# M4-Shim-1.net
KiCad netlist of a schematic drawn in EAGLE
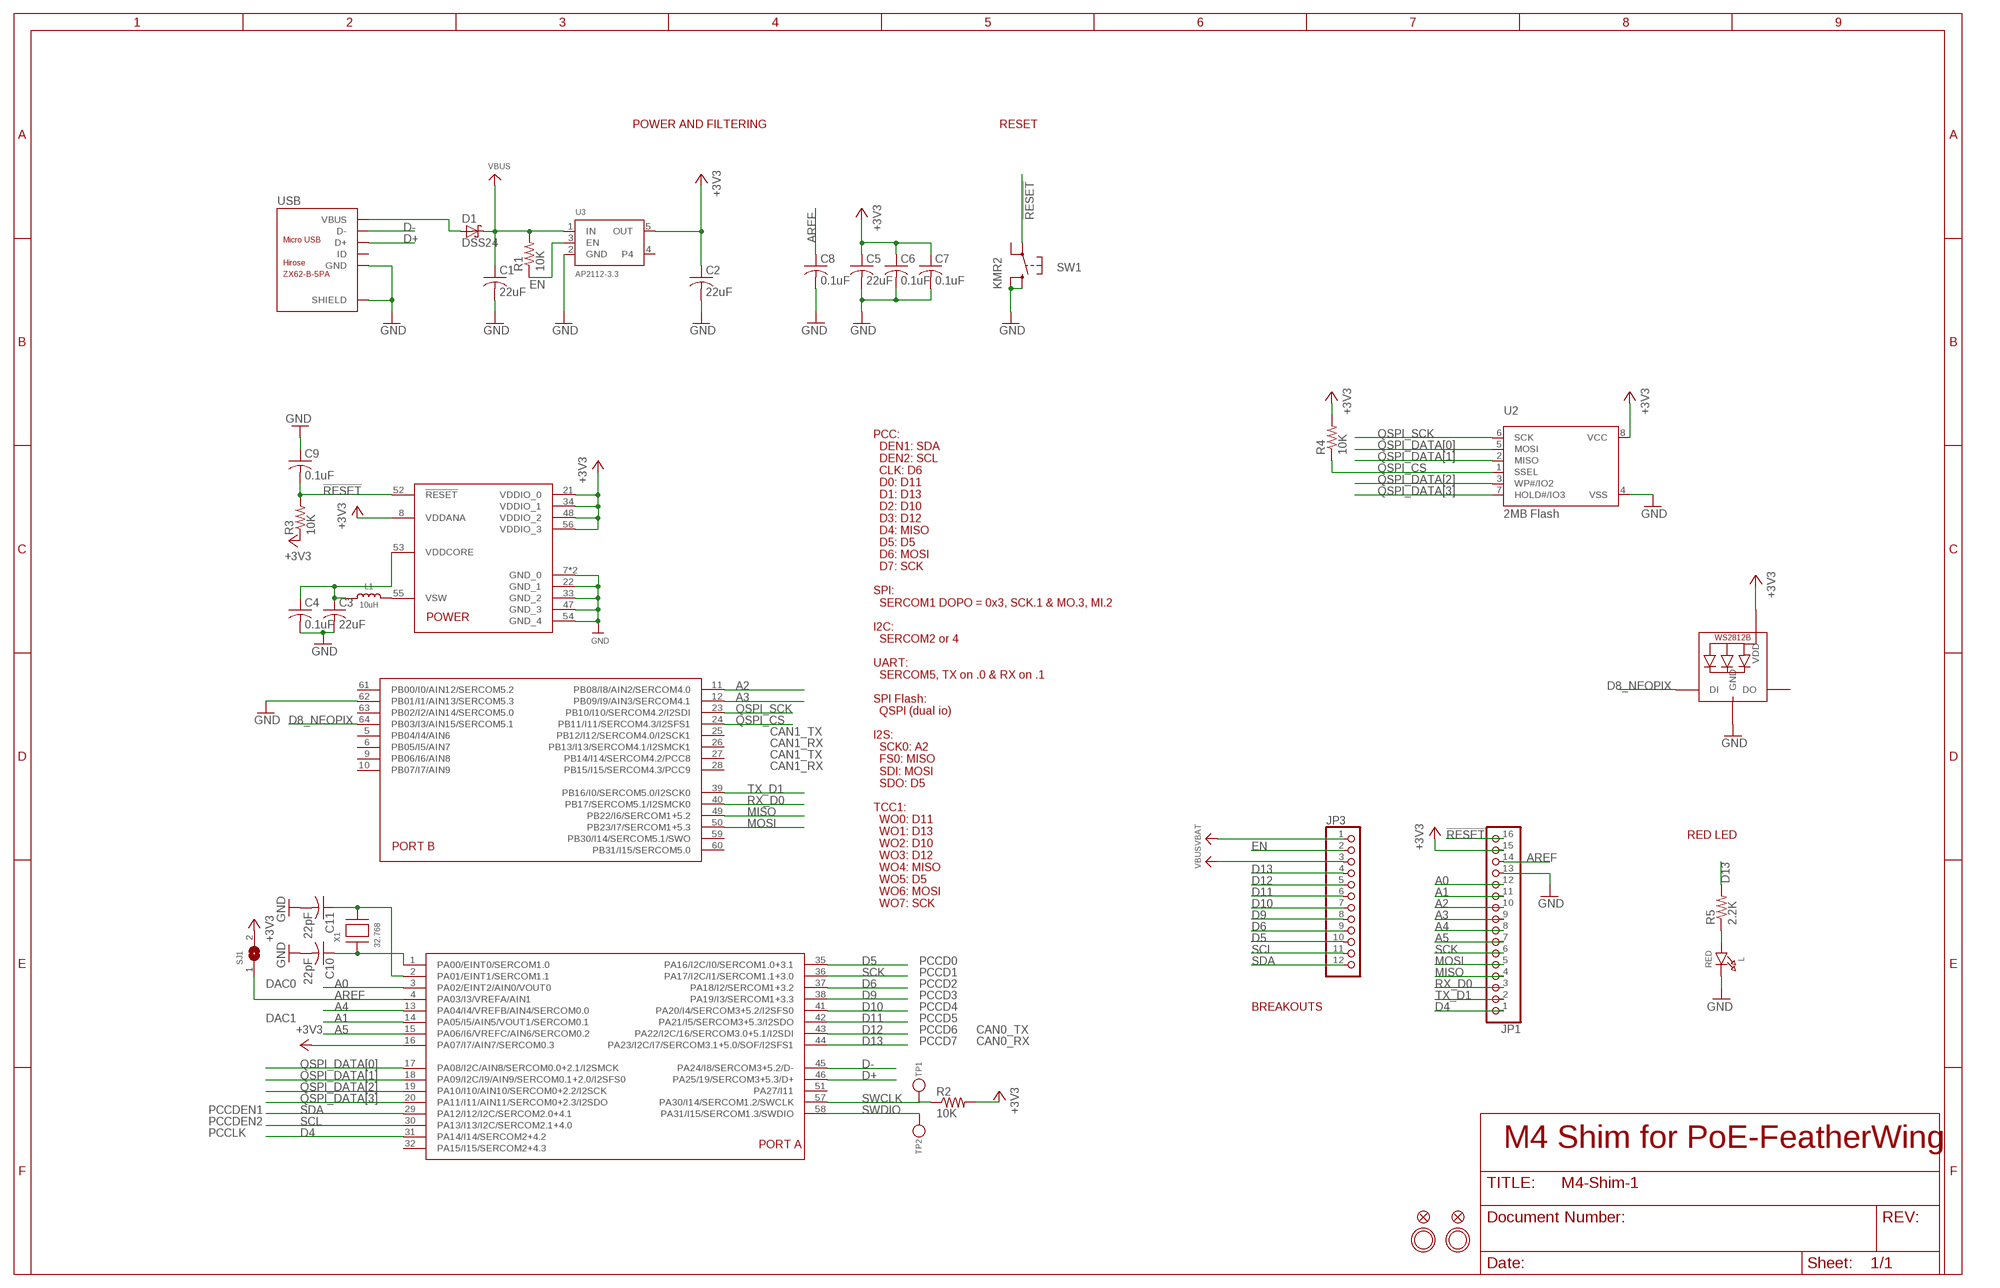
[diagram p0: schematic, sheet 1]

(export (version "E")
  (design (tool "Eeschema 10.0.6"))
  (components
    (comp (ref "C1")
      (value "22uF")
      (footprint "eagle-import:C0805K")
      (libsource (lib "eagle-import") (part "C-USC0805K"))
    )
    (comp (ref "C2")
      (value "22uF")
      (footprint "eagle-import:C0805K")
      (libsource (lib "eagle-import") (part "C-USC0805K"))
    )
    (comp (ref "C3")
      (value "22uF")
      (footprint "eagle-import:C0805K")
      (libsource (lib "eagle-import") (part "C-USC0805K"))
    )
    (comp (ref "C4")
      (value "0.1uF")
      (footprint "eagle-import:C0402K")
      (libsource (lib "eagle-import") (part "C-USC0402K"))
    )
    (comp (ref "C5")
      (value "22uF")
      (footprint "eagle-import:C0805K")
      (libsource (lib "eagle-import") (part "C-USC0805K"))
    )
    (comp (ref "C6")
      (value "0.1uF")
      (footprint "eagle-import:C0402K")
      (libsource (lib "eagle-import") (part "C-USC0402K"))
    )
    (comp (ref "C7")
      (value "0.1uF")
      (footprint "eagle-import:C0402K")
      (libsource (lib "eagle-import") (part "C-USC0402K"))
    )
    (comp (ref "C8")
      (value "0.1uF")
      (footprint "eagle-import:C0402K")
      (libsource (lib "eagle-import") (part "C-USC0402K"))
    )
    (comp (ref "C9")
      (value "0.1uF")
      (footprint "eagle-import:C0402K")
      (libsource (lib "eagle-import") (part "C-USC0402K"))
    )
    (comp (ref "C10")
      (value "22pF")
      (footprint "eagle-import:C0402K")
      (libsource (lib "eagle-import") (part "C-USC0402K"))
    )
    (comp (ref "C11")
      (value "22pF")
      (footprint "eagle-import:C0402K")
      (libsource (lib "eagle-import") (part "C-USC0402K"))
    )
    (comp (ref "D1")
      (value "DSS24")
      (footprint "eagle-import:SOD123FL")
      (libsource (lib "eagle-import") (part "DSS24"))
    )
    (comp (ref "JP1")
      (value "HEADER-1X16ROUND")
      (footprint "eagle-import:1X16_ROUND")
      (libsource (lib "eagle-import") (part "HEADER-1X16ROUND"))
    )
    (comp (ref "JP3")
      (value "HEADER-1X12")
      (footprint "eagle-import:1X12_ROUND")
      (libsource (lib "eagle-import") (part "HEADER-1X12"))
    )
    (comp (ref "L")
      (value "RED")
      (footprint "eagle-import:CHIPLED_0805_NOOUTLINE")
      (libsource (lib "eagle-import") (part "LED0805_NOOUTLINE"))
    )
    (comp (ref "L1")
      (value "10uH")
      (footprint "eagle-import:INDUCTOR_1007")
      (libsource (lib "eagle-import") (part "INDUCTOR"))
    )
    (comp (ref "LED1")
      (value "WS2812B3535")
      (footprint "eagle-import:LED3535")
      (libsource (lib "eagle-import") (part "WS2812B3535"))
    )
    (comp (ref "R1")
      (value "10K")
      (footprint "eagle-import:R0402")
      (libsource (lib "eagle-import") (part "R-US_R0402"))
    )
    (comp (ref "R2")
      (value "10K")
      (footprint "eagle-import:R0402")
      (libsource (lib "eagle-import") (part "R-US_R0402"))
    )
    (comp (ref "R3")
      (value "10K")
      (footprint "eagle-import:R0402")
      (libsource (lib "eagle-import") (part "R-US_R0402"))
    )
    (comp (ref "R4")
      (value "10K")
      (footprint "eagle-import:R0402")
      (libsource (lib "eagle-import") (part "R-US_R0402"))
    )
    (comp (ref "R5")
      (value "2.2K")
      (footprint "eagle-import:R0402")
      (libsource (lib "eagle-import") (part "R-US_R0402"))
    )
    (comp (ref "SJ1")
      (value "SOLDERJUMPERCLOSED")
      (footprint "eagle-import:SOLDERJUMPER_CLOSEDWIRE")
      (libsource (lib "eagle-import") (part "SOLDERJUMPERCLOSED"))
    )
    (comp (ref "SW1")
      (value "KMR2")
      (footprint "eagle-import:BTN_KMR2_4.6X2.8")
      (libsource (lib "eagle-import") (part "SWITCH_TACT_SMT4.6X2.8"))
    )
    (comp (ref "TP1")
      (value "TESTPOINTROUND1.5MM")
      (footprint "eagle-import:TESTPOINT_ROUND_1.5MM")
      (libsource (lib "eagle-import") (part "TESTPOINTROUND1.5MM"))
    )
    (comp (ref "TP2")
      (value "TESTPOINTROUND1.5MM")
      (footprint "eagle-import:TESTPOINT_ROUND_1.5MM")
      (libsource (lib "eagle-import") (part "TESTPOINTROUND1.5MM"))
    )
    (comp (ref "U$31")
      (value "MOUNTINGHOLE2.5")
      (footprint "eagle-import:MOUNTINGHOLE_2.5_PLATED")
      (libsource (lib "eagle-import") (part "MOUNTINGHOLE2.5"))
    )
    (comp (ref "U$32")
      (value "MOUNTINGHOLE2.5")
      (footprint "eagle-import:MOUNTINGHOLE_2.5_PLATED")
      (libsource (lib "eagle-import") (part "MOUNTINGHOLE2.5"))
    )
    (comp (ref "U$34")
      (value "FIDUCIAL_1MM")
      (footprint "eagle-import:FIDUCIAL_1MM")
      (libsource (lib "eagle-import") (part "FIDUCIAL_1MM"))
    )
    (comp (ref "U$35")
      (value "FIDUCIAL_1MM")
      (footprint "eagle-import:FIDUCIAL_1MM")
      (libsource (lib "eagle-import") (part "FIDUCIAL_1MM"))
    )
    (comp (ref "U1")
      (value "ATSAMD51J")
      (footprint "eagle-import:PQFN64-1")
      (libsource (lib "eagle-import") (part "ATSAMD51J"))
    )
    (comp (ref "U2")
      (value "2MB Flash")
      (footprint "eagle-import:USON8")
      (libsource (lib "eagle-import") (part "SPIFLASH_8PINUX"))
    )
    (comp (ref "U3")
      (value "AP2112-3.3")
      (footprint "eagle-import:SOT23-5")
      (libsource (lib "eagle-import") (part "VREG_SOT23-5"))
    )
    (comp (ref "USB")
      (value "ZX62-B-5PA")
      (footprint "eagle-import:MICRO-USB5+6P-SMD-0.65-AB")
      (libsource (lib "eagle-import") (part "MICRO-USB-SMD(ZX62-B-5PA)"))
    )
    (comp (ref "X1")
      (value "32.768")
      (footprint "eagle-import:XTAL3215")
      (libsource (lib "eagle-import") (part "XTAL-3.2X1.5"))
    )
  )
  (nets
    (net (code "1") (name "+3V3") (class "Default")
      (node (ref "C2") (pin "1") (pinfunction "1_1") (pintype "passive"))
      (node (ref "C5") (pin "1") (pinfunction "1_1") (pintype "passive"))
      (node (ref "C6") (pin "1") (pinfunction "1_1") (pintype "passive"))
      (node (ref "C7") (pin "1") (pinfunction "1_1") (pintype "passive"))
      (node (ref "JP1") (pin "15") (pinfunction "15_15") (pintype "passive"))
      (node (ref "LED1") (pin "2") (pinfunction "VDD_2") (pintype "power_in"))
      (node (ref "R2") (pin "2") (pinfunction "2_2") (pintype "passive"))
      (node (ref "R3") (pin "1") (pinfunction "1_1") (pintype "passive"))
      (node (ref "R4") (pin "2") (pinfunction "2_2") (pintype "passive"))
      (node (ref "SJ1") (pin "2") (pinfunction "2_2") (pintype "passive"))
      (node (ref "U1") (pin "16") (pinfunction "PA07/I7/AIN7/SERCOM0.3_16") (pintype "bidirectional"))
      (node (ref "U1") (pin "21") (pinfunction "VDDIO_0_21") (pintype "bidirectional"))
      (node (ref "U1") (pin "34") (pinfunction "VDDIO_1_34") (pintype "bidirectional"))
      (node (ref "U1") (pin "48") (pinfunction "VDDIO_2_48") (pintype "bidirectional"))
      (node (ref "U1") (pin "56") (pinfunction "VDDIO_3_56") (pintype "bidirectional"))
      (node (ref "U1") (pin "8") (pinfunction "VDDANA_8") (pintype "bidirectional"))
      (node (ref "U2") (pin "8") (pinfunction "VCC_8") (pintype "bidirectional"))
      (node (ref "U3") (pin "5") (pinfunction "OUT_5") (pintype "power_in"))
    )
    (net (code "2") (name "/A0") (class "Default")
      (node (ref "JP1") (pin "12") (pinfunction "12_12") (pintype "passive"))
      (node (ref "U1") (pin "3") (pinfunction "PA02/EINT2/AIN0/VOUT0_3") (pintype "bidirectional"))
    )
    (net (code "3") (name "/A1") (class "Default")
      (node (ref "JP1") (pin "11") (pinfunction "11_11") (pintype "passive"))
      (node (ref "U1") (pin "14") (pinfunction "PA05/I5/AIN5/VOUT1/SERCOM0.1_14") (pintype "bidirectional"))
    )
    (net (code "4") (name "/A2") (class "Default")
      (node (ref "JP1") (pin "10") (pinfunction "10_10") (pintype "passive"))
      (node (ref "U1") (pin "11") (pinfunction "PB08/I8/AIN2/SERCOM4.0_11") (pintype "bidirectional"))
    )
    (net (code "5") (name "/A3") (class "Default")
      (node (ref "JP1") (pin "9") (pinfunction "9_9") (pintype "passive"))
      (node (ref "U1") (pin "12") (pinfunction "PB09/I9/AIN3/SERCOM4.1_12") (pintype "bidirectional"))
    )
    (net (code "6") (name "/A4") (class "Default")
      (node (ref "JP1") (pin "8") (pinfunction "8_8") (pintype "passive"))
      (node (ref "U1") (pin "13") (pinfunction "PA04/I4/VREFB/AIN4/SERCOM0.0_13") (pintype "bidirectional"))
    )
    (net (code "7") (name "/A5") (class "Default")
      (node (ref "JP1") (pin "7") (pinfunction "7_7") (pintype "passive"))
      (node (ref "U1") (pin "15") (pinfunction "PA06/I6/VREFC/AIN6/SERCOM0.2_15") (pintype "bidirectional"))
    )
    (net (code "8") (name "/AREF") (class "Default")
      (node (ref "C8") (pin "1") (pinfunction "1_1") (pintype "passive"))
      (node (ref "JP1") (pin "14") (pinfunction "14_14") (pintype "passive"))
      (node (ref "SJ1") (pin "1") (pinfunction "1_1") (pintype "passive"))
      (node (ref "U1") (pin "4") (pinfunction "PA03/I3/VREFA/AIN1_4") (pintype "bidirectional"))
    )
    (net (code "9") (name "/D+") (class "Default")
      (node (ref "U1") (pin "46") (pinfunction "PA25/19/SERCOM3+5.3/D+_46") (pintype "bidirectional"))
      (node (ref "USB") (pin "3") (pinfunction "D+_3") (pintype "bidirectional"))
    )
    (net (code "10") (name "/D-") (class "Default")
      (node (ref "U1") (pin "45") (pinfunction "PA24/I8/SERCOM3+5.2/D-_45") (pintype "bidirectional"))
      (node (ref "USB") (pin "2") (pinfunction "D-_2") (pintype "bidirectional"))
    )
    (net (code "11") (name "/D4") (class "Default")
      (node (ref "JP1") (pin "1") (pinfunction "1_1") (pintype "passive"))
      (node (ref "U1") (pin "31") (pinfunction "PA14/I14/SERCOM2+4.2_31") (pintype "bidirectional"))
    )
    (net (code "12") (name "/D5") (class "Default")
      (node (ref "JP3") (pin "10") (pinfunction "10_10") (pintype "passive"))
      (node (ref "U1") (pin "35") (pinfunction "PA16/I2C/I0/SERCOM1.0+3.1_35") (pintype "bidirectional"))
    )
    (net (code "13") (name "/D6") (class "Default")
      (node (ref "JP3") (pin "9") (pinfunction "9_9") (pintype "passive"))
      (node (ref "U1") (pin "37") (pinfunction "PA18/I2/SERCOM1+3.2_37") (pintype "bidirectional"))
    )
    (net (code "14") (name "/D8_NEOPIX") (class "Default")
      (node (ref "LED1") (pin "1") (pinfunction "DI_1") (pintype "input"))
      (node (ref "U1") (pin "64") (pinfunction "PB03/I3/AIN15/SERCOM5.1_64") (pintype "bidirectional"))
    )
    (net (code "15") (name "/D9") (class "Default")
      (node (ref "JP3") (pin "8") (pinfunction "8_8") (pintype "passive"))
      (node (ref "U1") (pin "38") (pinfunction "PA19/I3/SERCOM1+3.3_38") (pintype "bidirectional"))
    )
    (net (code "16") (name "/D10") (class "Default")
      (node (ref "JP3") (pin "7") (pinfunction "7_7") (pintype "passive"))
      (node (ref "U1") (pin "41") (pinfunction "PA20/I4/SERCOM3+5.2/I2SFS0_41") (pintype "bidirectional"))
    )
    (net (code "17") (name "/D11") (class "Default")
      (node (ref "JP3") (pin "6") (pinfunction "6_6") (pintype "passive"))
      (node (ref "U1") (pin "42") (pinfunction "PA21/I5/SERCOM3+5.3/I2SDO_42") (pintype "bidirectional"))
    )
    (net (code "18") (name "/D12") (class "Default")
      (node (ref "JP3") (pin "5") (pinfunction "5_5") (pintype "passive"))
      (node (ref "U1") (pin "43") (pinfunction "PA22/I2C/16/SERCOM3.0+5.1/I2SDI_43") (pintype "bidirectional"))
    )
    (net (code "19") (name "/D13") (class "Default")
      (node (ref "JP3") (pin "4") (pinfunction "4_4") (pintype "passive"))
      (node (ref "R5") (pin "2") (pinfunction "2_2") (pintype "passive"))
      (node (ref "U1") (pin "44") (pinfunction "PA23/I2C/I7/SERCOM3.1+5.0/SOF/I2SFS1_44") (pintype "bidirectional"))
    )
    (net (code "20") (name "/EN") (class "Default")
      (node (ref "JP3") (pin "2") (pinfunction "2_2") (pintype "passive"))
      (node (ref "R1") (pin "1") (pinfunction "1_1") (pintype "passive"))
      (node (ref "U3") (pin "3") (pinfunction "EN_3") (pintype "input"))
    )
    (net (code "21") (name "/MISO") (class "Default")
      (node (ref "JP1") (pin "4") (pinfunction "4_4") (pintype "passive"))
      (node (ref "U1") (pin "49") (pinfunction "PB22/I6/SERCOM1+5.2_49") (pintype "bidirectional"))
    )
    (net (code "22") (name "/MOSI") (class "Default")
      (node (ref "JP1") (pin "5") (pinfunction "5_5") (pintype "passive"))
      (node (ref "U1") (pin "50") (pinfunction "PB23/I7/SERCOM1+5.3_50") (pintype "bidirectional"))
    )
    (net (code "23") (name "/QSPI_CS") (class "Default")
      (node (ref "R4") (pin "1") (pinfunction "1_1") (pintype "passive"))
      (node (ref "U1") (pin "24") (pinfunction "PB11/I11/SERCOM4.3/I2SFS1_24") (pintype "bidirectional"))
      (node (ref "U2") (pin "1") (pinfunction "SSEL_1") (pintype "bidirectional"))
    )
    (net (code "24") (name "/QSPI_DATA[0]") (class "Default")
      (node (ref "U1") (pin "17") (pinfunction "PA08/I2C/AIN8/SERCOM0.0+2.1/I2SMCK_17") (pintype "bidirectional"))
      (node (ref "U2") (pin "5") (pinfunction "MOSI_5") (pintype "bidirectional"))
    )
    (net (code "25") (name "/QSPI_DATA[1]") (class "Default")
      (node (ref "U1") (pin "18") (pinfunction "PA09/I2C/I9/AIN9/SERCOM0.1+2.0/I2SFS0_18") (pintype "bidirectional"))
      (node (ref "U2") (pin "2") (pinfunction "MISO_2") (pintype "bidirectional"))
    )
    (net (code "26") (name "/QSPI_DATA[2]") (class "Default")
      (node (ref "U1") (pin "19") (pinfunction "PA10/I10/AIN10/SERCOM0+2.2/I2SCK_19") (pintype "bidirectional"))
      (node (ref "U2") (pin "3") (pinfunction "WP#/IO2_3") (pintype "bidirectional"))
    )
    (net (code "27") (name "/QSPI_DATA[3]") (class "Default")
      (node (ref "U1") (pin "20") (pinfunction "PA11/I11/AIN11/SERCOM0+2.3/I2SDO_20") (pintype "bidirectional"))
      (node (ref "U2") (pin "7") (pinfunction "HOLD#/IO3_7") (pintype "bidirectional"))
    )
    (net (code "28") (name "/QSPI_SCK") (class "Default")
      (node (ref "U1") (pin "23") (pinfunction "PB10/I10/SERCOM4.2/I2SDI_23") (pintype "bidirectional"))
      (node (ref "U2") (pin "6") (pinfunction "SCK_6") (pintype "bidirectional"))
    )
    (net (code "29") (name "/RX_D0") (class "Default")
      (node (ref "JP1") (pin "3") (pinfunction "3_3") (pintype "passive"))
      (node (ref "U1") (pin "40") (pinfunction "PB17/SERCOM5.1/I2SMCK0_40") (pintype "bidirectional"))
    )
    (net (code "30") (name "/SCK") (class "Default")
      (node (ref "JP1") (pin "6") (pinfunction "6_6") (pintype "passive"))
      (node (ref "U1") (pin "36") (pinfunction "PA17/I2C/I1/SERCOM1.1+3.0_36") (pintype "bidirectional"))
    )
    (net (code "31") (name "/SCL") (class "Default")
      (node (ref "JP3") (pin "11") (pinfunction "11_11") (pintype "passive"))
      (node (ref "U1") (pin "30") (pinfunction "PA13/I13/I2C/SERCOM2.1+4.0_30") (pintype "bidirectional"))
    )
    (net (code "32") (name "/SDA") (class "Default")
      (node (ref "JP3") (pin "12") (pinfunction "12_12") (pintype "passive"))
      (node (ref "U1") (pin "29") (pinfunction "PA12/I12/I2C/SERCOM2.0+4.1_29") (pintype "bidirectional"))
    )
    (net (code "33") (name "/SWCLK") (class "Default")
      (node (ref "R2") (pin "1") (pinfunction "1_1") (pintype "passive"))
      (node (ref "TP1") (pin "P$1") (pinfunction "P$1_P$1") (pintype "bidirectional"))
      (node (ref "U1") (pin "57") (pinfunction "PA30/I14/SERCOM1.2/SWCLK_57") (pintype "bidirectional"))
    )
    (net (code "34") (name "/SWDIO") (class "Default")
      (node (ref "TP2") (pin "P$1") (pinfunction "P$1_P$1") (pintype "bidirectional"))
      (node (ref "U1") (pin "58") (pinfunction "PA31/I15/SERCOM1.3/SWDIO_58") (pintype "bidirectional"))
    )
    (net (code "35") (name "/TX_D1") (class "Default")
      (node (ref "JP1") (pin "2") (pinfunction "2_2") (pintype "passive"))
      (node (ref "U1") (pin "39") (pinfunction "PB16/I0/SERCOM5.0/I2SCK0_39") (pintype "bidirectional"))
    )
    (net (code "36") (name "/~{RESET}") (class "Default")
      (node (ref "C9") (pin "2") (pinfunction "2_2") (pintype "passive"))
      (node (ref "JP1") (pin "16") (pinfunction "16_16") (pintype "passive"))
      (node (ref "R3") (pin "2") (pinfunction "2_2") (pintype "passive"))
      (node (ref "SW1") (pin "A") (pinfunction "P_A") (pintype "passive"))
      (node (ref "U1") (pin "52") (pinfunction "~{RESET}_52") (pintype "bidirectional"))
    )
    (net (code "37") (name "GND") (class "Default")
      (node (ref "C1") (pin "2") (pinfunction "2_2") (pintype "passive"))
      (node (ref "C10") (pin "2") (pinfunction "2_2") (pintype "passive"))
      (node (ref "C11") (pin "2") (pinfunction "2_2") (pintype "passive"))
      (node (ref "C2") (pin "2") (pinfunction "2_2") (pintype "passive"))
      (node (ref "C3") (pin "2") (pinfunction "2_2") (pintype "passive"))
      (node (ref "C4") (pin "2") (pinfunction "2_2") (pintype "passive"))
      (node (ref "C5") (pin "2") (pinfunction "2_2") (pintype "passive"))
      (node (ref "C6") (pin "2") (pinfunction "2_2") (pintype "passive"))
      (node (ref "C7") (pin "2") (pinfunction "2_2") (pintype "passive"))
      (node (ref "C8") (pin "2") (pinfunction "2_2") (pintype "passive"))
      (node (ref "C9") (pin "1") (pinfunction "1_1") (pintype "passive"))
      (node (ref "JP1") (pin "13") (pinfunction "13_13") (pintype "passive"))
      (node (ref "L") (pin "C") (pinfunction "C_C") (pintype "passive"))
      (node (ref "LED1") (pin "4") (pinfunction "GND_4") (pintype "power_in"))
      (node (ref "SW1") (pin "B") (pinfunction "S_B") (pintype "passive"))
      (node (ref "SW1") (pin "B'") (pinfunction "S1_B'") (pintype "passive"))
      (node (ref "U1") (pin "22") (pinfunction "GND_1_22") (pintype "bidirectional"))
      (node (ref "U1") (pin "33") (pinfunction "GND_2_33") (pintype "bidirectional"))
      (node (ref "U1") (pin "47") (pinfunction "GND_3_47") (pintype "bidirectional"))
      (node (ref "U1") (pin "54") (pinfunction "GND_4_54") (pintype "bidirectional"))
      (node (ref "U1") (pin "62") (pinfunction "PB01/I1/AIN13/SERCOM5.3_62") (pintype "bidirectional"))
      (node (ref "U1") (pin "7") (pinfunction "GND_0_7") (pintype "bidirectional"))
      (node (ref "U1") (pin "EXP") (pinfunction "GND_0_EXP") (pintype "bidirectional"))
      (node (ref "U2") (pin "4") (pinfunction "VSS_4") (pintype "bidirectional"))
      (node (ref "U3") (pin "2") (pinfunction "GND_2") (pintype "power_in"))
      (node (ref "USB") (pin "5") (pinfunction "GND_5") (pintype "power_in"))
      (node (ref "USB") (pin "P1") (pinfunction "SHIELD_P1") (pintype "power_in"))
      (node (ref "USB") (pin "P2") (pinfunction "SHIELD_P2") (pintype "power_in"))
      (node (ref "USB") (pin "P3") (pinfunction "SHIELD_P3") (pintype "power_in"))
      (node (ref "USB") (pin "P4") (pinfunction "SHIELD_P4") (pintype "power_in"))
      (node (ref "USB") (pin "P5") (pinfunction "SHIELD_P5") (pintype "power_in"))
      (node (ref "USB") (pin "P6") (pinfunction "SHIELD_P6") (pintype "power_in"))
    )
    (net (code "38") (name "Net-(L-PadA)") (class "Default")
      (node (ref "L") (pin "A") (pinfunction "A_A") (pintype "passive"))
      (node (ref "R5") (pin "1") (pinfunction "1_1") (pintype "passive"))
    )
    (net (code "39") (name "Net-(L1-1)") (class "Default")
      (node (ref "C3") (pin "1") (pinfunction "1_1") (pintype "passive"))
      (node (ref "C4") (pin "1") (pinfunction "1_1") (pintype "passive"))
      (node (ref "L1") (pin "P$1") (pinfunction "1_P$1") (pintype "passive"))
      (node (ref "U1") (pin "53") (pinfunction "VDDCORE_53") (pintype "bidirectional"))
    )
    (net (code "40") (name "Net-(L1-2)") (class "Default")
      (node (ref "L1") (pin "P$2") (pinfunction "2_P$2") (pintype "passive"))
      (node (ref "U1") (pin "55") (pinfunction "VSW_55") (pintype "bidirectional"))
    )
    (net (code "41") (name "Net-(U1A-PA00{slash}EINT0{slash}SERCOM1.0)") (class "Default")
      (node (ref "C10") (pin "1") (pinfunction "1_1") (pintype "passive"))
      (node (ref "U1") (pin "1") (pinfunction "PA00/EINT0/SERCOM1.0_1") (pintype "bidirectional"))
      (node (ref "X1") (pin "P$1") (pinfunction "P$1_P$1") (pintype "bidirectional"))
    )
    (net (code "42") (name "Net-(U1A-PA01{slash}EINT1{slash}SERCOM1.1)") (class "Default")
      (node (ref "C11") (pin "1") (pinfunction "1_1") (pintype "passive"))
      (node (ref "U1") (pin "2") (pinfunction "PA01/EINT1/SERCOM1.1_2") (pintype "bidirectional"))
      (node (ref "X1") (pin "P$2") (pinfunction "P$2_P$2") (pintype "bidirectional"))
    )
    (net (code "43") (name "Net-(USB-VBUS)") (class "Default")
      (node (ref "D1") (pin "A") (pinfunction "A_A") (pintype "passive"))
      (node (ref "USB") (pin "1") (pinfunction "VBUS_1") (pintype "power_in"))
    )
    (net (code "44") (name "VBAT") (class "Default")
      (node (ref "JP3") (pin "1") (pinfunction "1_1") (pintype "passive"))
    )
    (net (code "45") (name "VBUS") (class "Default")
      (node (ref "C1") (pin "1") (pinfunction "1_1") (pintype "passive"))
      (node (ref "D1") (pin "C") (pinfunction "C_C") (pintype "passive"))
      (node (ref "JP3") (pin "3") (pinfunction "3_3") (pintype "passive"))
      (node (ref "R1") (pin "2") (pinfunction "2_2") (pintype "passive"))
      (node (ref "U3") (pin "1") (pinfunction "IN_1") (pintype "power_in"))
    )
    (net (code "46") (name "unconnected-(LED1-DO-Pad3)") (class "Default")
      (node (ref "LED1") (pin "3") (pinfunction "DO_3") (pintype "output"))
    )
    (net (code "47") (name "unconnected-(SW1-P1-PadA')") (class "Default")
      (node (ref "SW1") (pin "A'") (pinfunction "P1_A'") (pintype "passive"))
    )
    (net (code "48") (name "unconnected-(U1A-PA15{slash}I15{slash}SERCOM2+4.3-Pad32)") (class "Default")
      (node (ref "U1") (pin "32") (pinfunction "PA15/I15/SERCOM2+4.3_32") (pintype "bidirectional"))
    )
    (net (code "49") (name "unconnected-(U1A-PA27{slash}I11-Pad51)") (class "Default")
      (node (ref "U1") (pin "51") (pinfunction "PA27/I11_51") (pintype "bidirectional"))
    )
    (net (code "50") (name "unconnected-(U1B-PB00{slash}I0{slash}AIN12{slash}SERCOM5.2-Pad61)") (class "Default")
      (node (ref "U1") (pin "61") (pinfunction "PB00/I0/AIN12/SERCOM5.2_61") (pintype "bidirectional"))
    )
    (net (code "51") (name "unconnected-(U1B-PB02{slash}I2{slash}AIN14{slash}SERCOM5.0-Pad63)") (class "Default")
      (node (ref "U1") (pin "63") (pinfunction "PB02/I2/AIN14/SERCOM5.0_63") (pintype "bidirectional"))
    )
    (net (code "52") (name "unconnected-(U1B-PB04{slash}I4{slash}AIN6-Pad5)") (class "Default")
      (node (ref "U1") (pin "5") (pinfunction "PB04/I4/AIN6_5") (pintype "bidirectional"))
    )
    (net (code "53") (name "unconnected-(U1B-PB05{slash}I5{slash}AIN7-Pad6)") (class "Default")
      (node (ref "U1") (pin "6") (pinfunction "PB05/I5/AIN7_6") (pintype "bidirectional"))
    )
    (net (code "54") (name "unconnected-(U1B-PB06{slash}I6{slash}AIN8-Pad9)") (class "Default")
      (node (ref "U1") (pin "9") (pinfunction "PB06/I6/AIN8_9") (pintype "bidirectional"))
    )
    (net (code "55") (name "unconnected-(U1B-PB07{slash}I7{slash}AIN9-Pad10)") (class "Default")
      (node (ref "U1") (pin "10") (pinfunction "PB07/I7/AIN9_10") (pintype "bidirectional"))
    )
    (net (code "56") (name "unconnected-(U1B-PB12{slash}I12{slash}SERCOM4.0{slash}I2SCK1-Pad25)") (class "Default")
      (node (ref "U1") (pin "25") (pinfunction "PB12/I12/SERCOM4.0/I2SCK1_25") (pintype "bidirectional"))
    )
    (net (code "57") (name "unconnected-(U1B-PB13{slash}I13{slash}SERCOM4.1{slash}I2SMCK1-Pad26)") (class "Default")
      (node (ref "U1") (pin "26") (pinfunction "PB13/I13/SERCOM4.1/I2SMCK1_26") (pintype "bidirectional"))
    )
    (net (code "58") (name "unconnected-(U1B-PB14{slash}I14{slash}SERCOM4.2{slash}PCC8-Pad27)") (class "Default")
      (node (ref "U1") (pin "27") (pinfunction "PB14/I14/SERCOM4.2/PCC8_27") (pintype "bidirectional"))
    )
    (net (code "59") (name "unconnected-(U1B-PB15{slash}I15{slash}SERCOM4.3{slash}PCC9-Pad28)") (class "Default")
      (node (ref "U1") (pin "28") (pinfunction "PB15/I15/SERCOM4.3/PCC9_28") (pintype "bidirectional"))
    )
    (net (code "60") (name "unconnected-(U1B-PB30{slash}I14{slash}SERCOM5.1{slash}SWO-Pad59)") (class "Default")
      (node (ref "U1") (pin "59") (pinfunction "PB30/I14/SERCOM5.1/SWO_59") (pintype "bidirectional"))
    )
    (net (code "61") (name "unconnected-(U1B-PB31{slash}I15{slash}SERCOM5.0-Pad60)") (class "Default")
      (node (ref "U1") (pin "60") (pinfunction "PB31/I15/SERCOM5.0_60") (pintype "bidirectional"))
    )
    (net (code "62") (name "unconnected-(U3-P4-Pad4)") (class "Default")
      (node (ref "U3") (pin "4") (pinfunction "P4_4") (pintype "bidirectional"))
    )
    (net (code "63") (name "unconnected-(USB-ID-Pad4)") (class "Default")
      (node (ref "USB") (pin "4") (pinfunction "ID_4") (pintype "bidirectional"))
    )
  )
)
